# SCH_ESP32-S2-UNO_Final_2023-12-28.net
KiCad netlist of a schematic drawn in EasyEDA
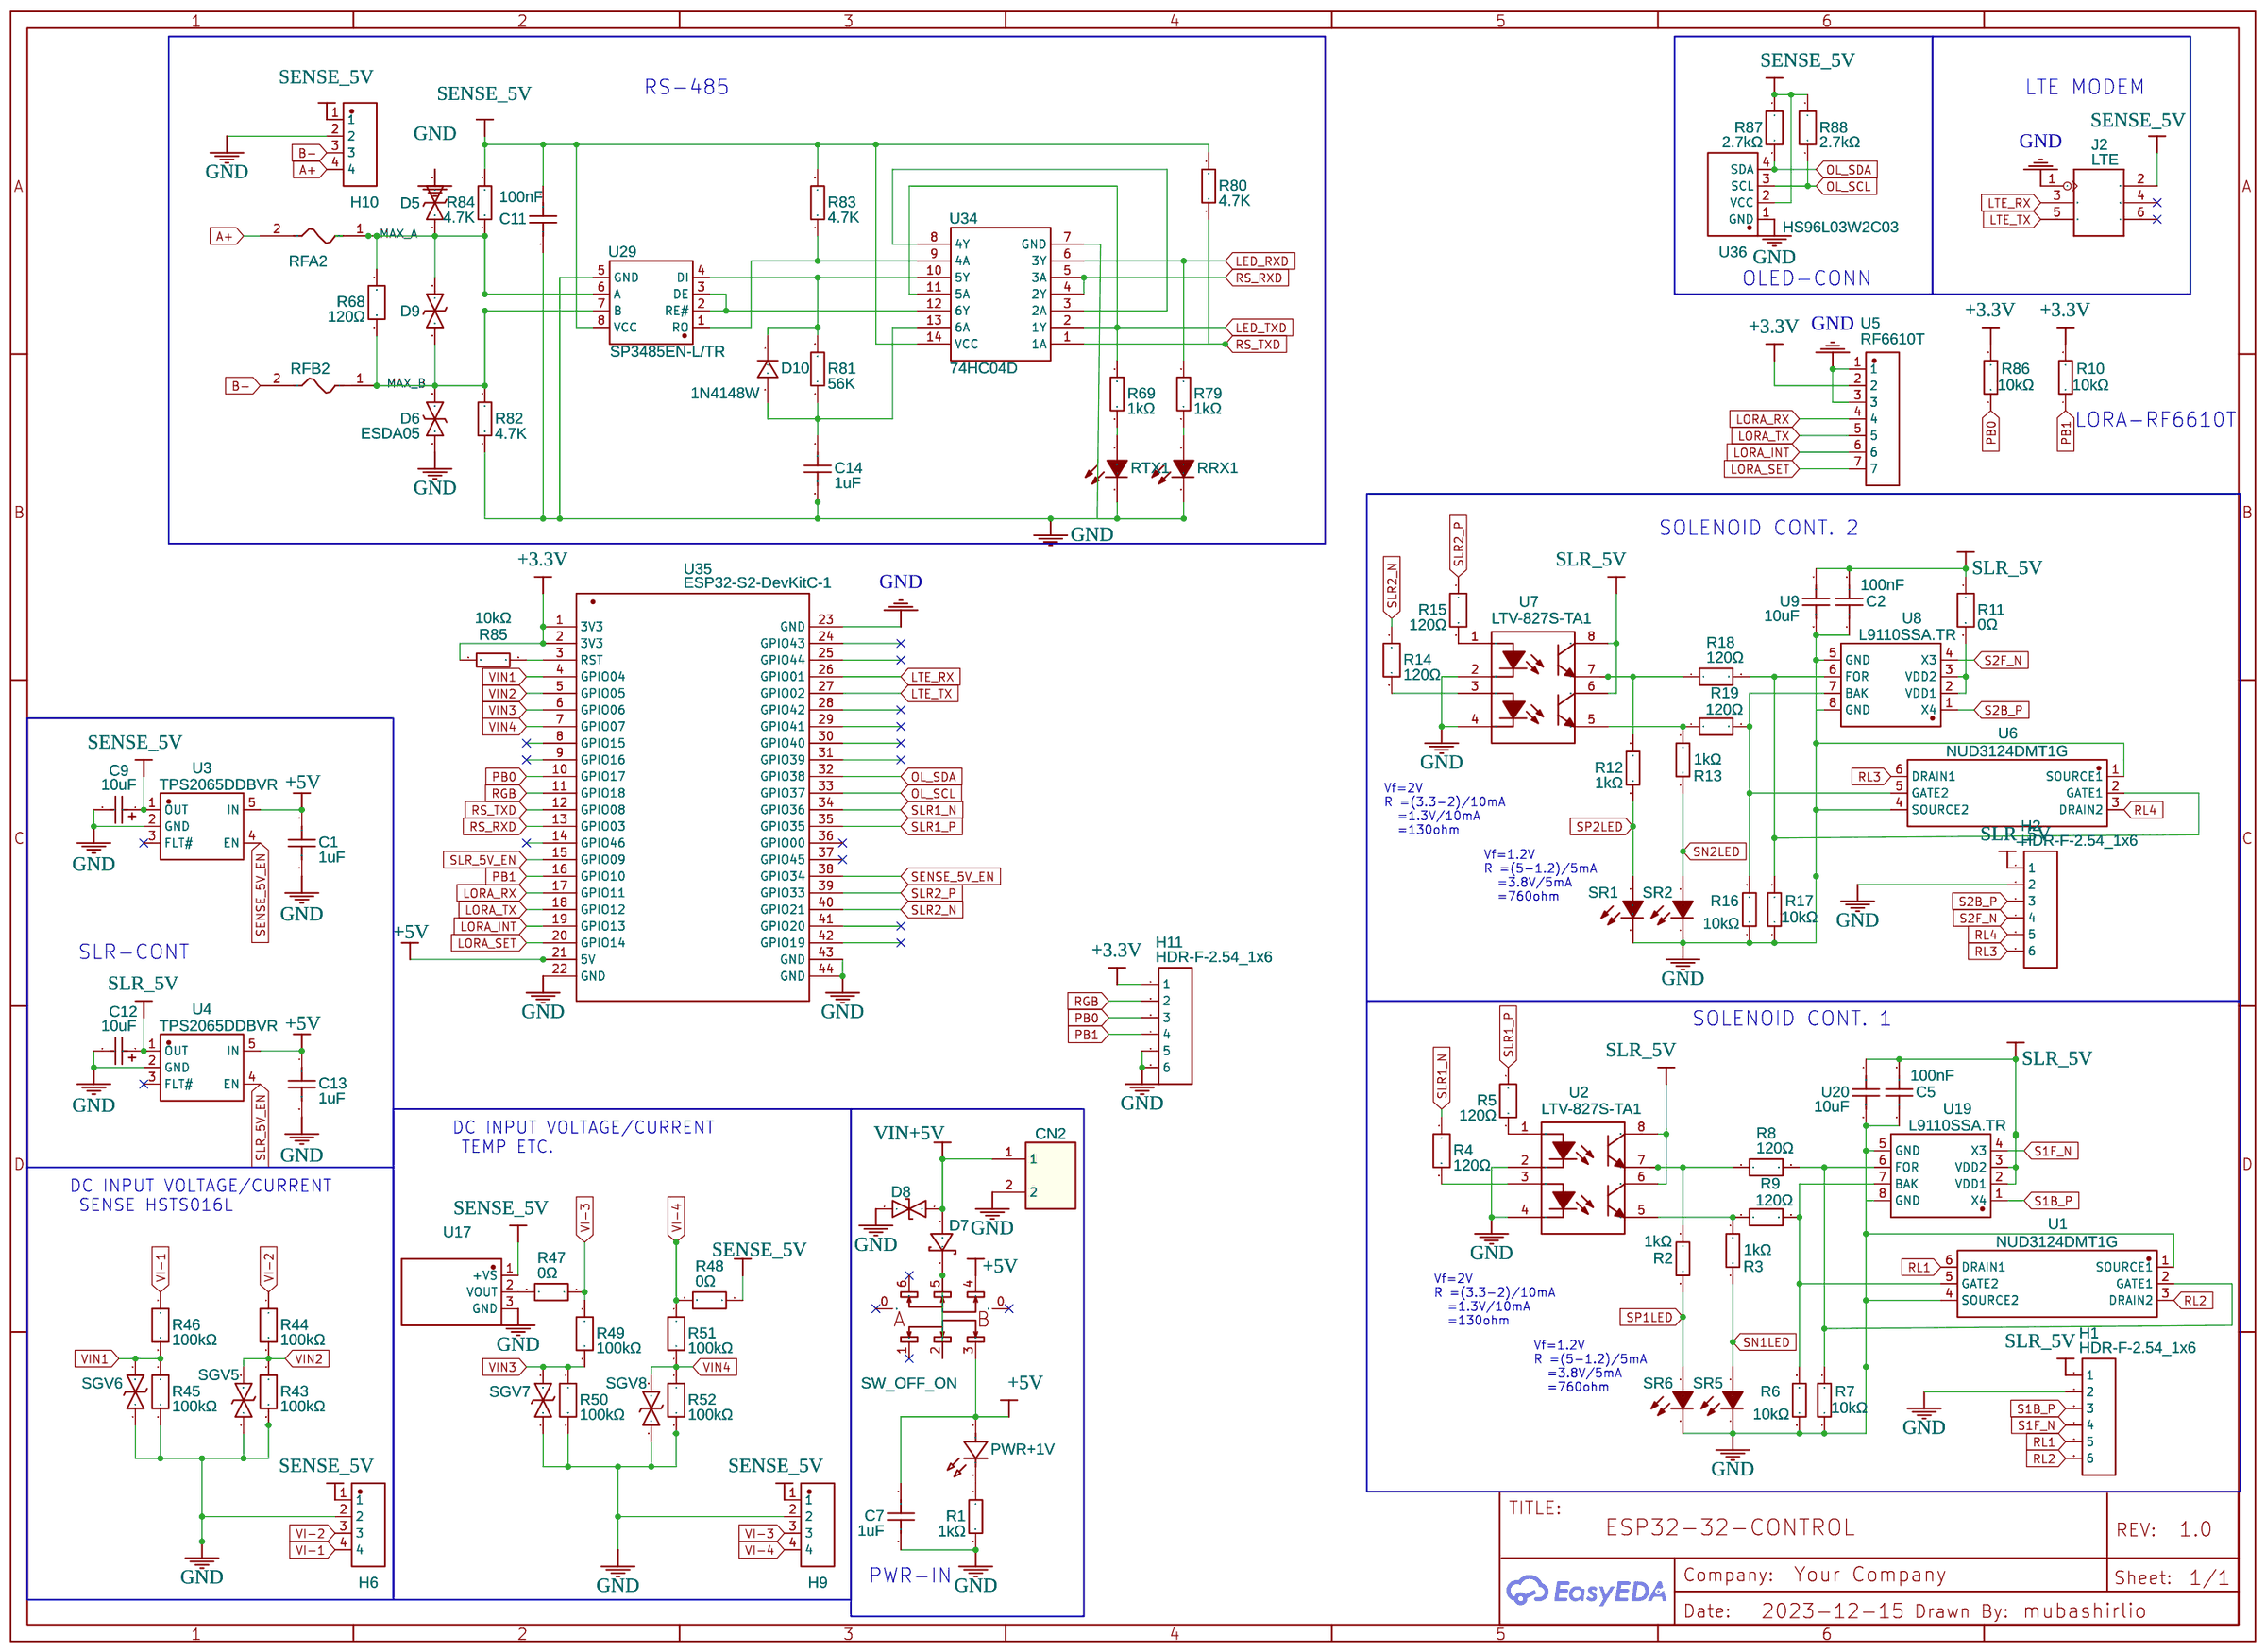
[diagram p0: schematic sheet]

(export (version "E")
  (design (tool "Eeschema 10.0.6"))
  (components
    (comp (ref "C1")
      (value "1uF")
      (fields
        (field (name "Manufacturer Part") "GRM155R61H105ME05D")
        (field (name "Manufacturer") "muRata(村田)")
      )
      (libsource (lib "") (part "GRM155R61H105ME05D"))
    )
    (comp (ref "C2")
      (value "100nF")
      (fields (field (name "Manufacturer Part") "C1005X5R0J104K050BA") (field (name "Manufacturer") "TDK"))
      (libsource (lib "") (part "C1005X5R0J104K050BA"))
    )
    (comp (ref "C5")
      (value "100nF")
      (fields (field (name "Manufacturer Part") "C1005X5R0J104K050BA") (field (name "Manufacturer") "TDK"))
      (libsource (lib "") (part "C1005X5R0J104K050BA"))
    )
    (comp (ref "C7")
      (value "1uF")
      (fields
        (field (name "Manufacturer Part") "GRM155R61H105ME05D")
        (field (name "Manufacturer") "muRata(村田)")
      )
      (libsource (lib "") (part "GRM155R61H105ME05D_1"))
    )
    (comp (ref "C9")
      (value "10uF")
      (fields
        (field (name "Manufacturer Part") "CA45A-A-16V-10uF-K")
        (field (name "Manufacturer") "CEC(振华新云)")
      )
      (libsource (lib "") (part "CA45A-A-16V-10UF-K"))
    )
    (comp (ref "C11")
      (value "100nF")
      (fields (field (name "Manufacturer Part") "C1005X5R0J104K050BA") (field (name "Manufacturer") "TDK"))
      (libsource (lib "") (part "C1005X5R0J104K050BA_1"))
    )
    (comp (ref "C12")
      (value "10uF")
      (fields
        (field (name "Manufacturer Part") "CA45A-A-16V-10uF-K")
        (field (name "Manufacturer") "CEC(振华新云)")
      )
      (libsource (lib "") (part "CA45A-A-16V-10UF-K"))
    )
    (comp (ref "C13")
      (value "1uF")
      (fields
        (field (name "Manufacturer Part") "GRM155R61H105ME05D")
        (field (name "Manufacturer") "muRata(村田)")
      )
      (libsource (lib "") (part "GRM155R61H105ME05D"))
    )
    (comp (ref "C14")
      (value "1uF")
      (fields
        (field (name "Manufacturer Part") "GRM155R61H105ME05D")
        (field (name "Manufacturer") "muRata(村田)")
      )
      (libsource (lib "") (part "GRM155R61H105ME05D"))
    )
    (comp (ref "CN2")
      (value "B2B-PH-K-S(LF)(SN)")
      (fields (field (name "Manufacturer") "JST"))
      (libsource (lib "") (part "B2B-PH-K-S(LF)(SN)"))
    )
    (comp (ref "D5")
      (value "ESDA05")
      (fields (field (name "Manufacturer") "Leiditech(雷卯电子)"))
      (libsource (lib "") (part "ESDA05_2"))
    )
    (comp (ref "D6")
      (value "ESDA05")
      (fields (field (name "Manufacturer") "Leiditech(雷卯电子)"))
      (libsource (lib "") (part "ESDA05_1"))
    )
    (comp (ref "D7")
      (value "BAT760-7")
      (fields (field (name "Manufacturer") "DIODES(美台)"))
      (libsource (lib "") (part "BAT760-7"))
    )
    (comp (ref "D8")
      (value "LESD5D5.0CT1G")
      (fields (field (name "Manufacturer") "LRC(乐山无线电)"))
      (libsource (lib "") (part "LESD5D5.0CT1G"))
    )
    (comp (ref "D9")
      (value "ESDA05")
      (fields (field (name "Manufacturer") "Leiditech(雷卯电子)"))
      (libsource (lib "") (part "ESDA05_2"))
    )
    (comp (ref "D10")
      (value "1N4148W")
      (fields (field (name "Manufacturer") "SEMTECH"))
      (libsource (lib "") (part "1N4148W_C81598"))
    )
    (comp (ref "H1") (value "HDR-F-2.54_1x6") (libsource (lib "") (part "HDR-F-2.54_1x6")))
    (comp (ref "H2") (value "HDR-F-2.54_1x6") (libsource (lib "") (part "HDR-F-2.54_1x6")))
    (comp (ref "H6")
      (value "X6511WV-04H-C30D60")
      (fields (field (name "Manufacturer") "XKB Connectivity(中国星坤)"))
      (libsource (lib "") (part "X6511WV-04H-C30D60"))
    )
    (comp (ref "H9")
      (value "X6511WV-04H-C30D60")
      (fields (field (name "Manufacturer") "XKB Connectivity(中国星坤)"))
      (libsource (lib "") (part "X6511WV-04H-C30D60"))
    )
    (comp (ref "H10")
      (value "X6511WV-04H-C30D60")
      (fields (field (name "Manufacturer") "XKB Connectivity(中国星坤)"))
      (libsource (lib "") (part "X6511WV-04H-C30D60"))
    )
    (comp (ref "H11") (value "HDR-F-2.54_1x6") (libsource (lib "") (part "HDR-F-2.54_1x6")))
    (comp (ref "J2") (value "LTE") (libsource (lib "") (part "MALE-HEADER(2X3P-2.54)")))
    (comp (ref "PWR+1V")
      (value "16-213/BHC-ZL1M2B6Y/3T")
      (fields (field (name "Manufacturer") "EVERLIGHT(亿光)"))
      (libsource (lib "") (part "16-213/BHC-ZL1M2B6Y/3T"))
    )
    (comp (ref "R1")
      (value "1kΩ")
      (fields (field (name "Manufacturer Part") "AR02DTD1001") (field (name "Manufacturer") "Viking(光颉)"))
      (libsource (lib "") (part "AR02DTD1001"))
    )
    (comp (ref "R2")
      (value "1kΩ")
      (fields (field (name "Manufacturer Part") "AR02DTD1001") (field (name "Manufacturer") "Viking(光颉)"))
      (libsource (lib "") (part "AR02DTD1001"))
    )
    (comp (ref "R3")
      (value "1kΩ")
      (fields (field (name "Manufacturer Part") "AR02DTD1001") (field (name "Manufacturer") "Viking(光颉)"))
      (libsource (lib "") (part "AR02DTD1001"))
    )
    (comp (ref "R4")
      (value "120Ω")
      (fields (field (name "Manufacturer Part") "RM04FTN1200") (field (name "Manufacturer") "大毅科技"))
      (libsource (lib "") (part "RM04FTN1200"))
    )
    (comp (ref "R5")
      (value "120Ω")
      (fields (field (name "Manufacturer Part") "RM04FTN1200") (field (name "Manufacturer") "大毅科技"))
      (libsource (lib "") (part "RM04FTN1200"))
    )
    (comp (ref "R6")
      (value "10kΩ")
      (fields
        (field (name "Manufacturer Part") "0402WGF1002TCE")
        (field (name "Manufacturer") "UNI-ROYAL(厚声)")
      )
      (libsource (lib "") (part "0402WGF1002TCE"))
    )
    (comp (ref "R7")
      (value "10kΩ")
      (fields
        (field (name "Manufacturer Part") "0402WGF1002TCE")
        (field (name "Manufacturer") "UNI-ROYAL(厚声)")
      )
      (libsource (lib "") (part "0402WGF1002TCE"))
    )
    (comp (ref "R8")
      (value "120Ω")
      (fields (field (name "Manufacturer Part") "RM04FTN1200") (field (name "Manufacturer") "大毅科技"))
      (libsource (lib "") (part "RM04FTN1200_1"))
    )
    (comp (ref "R9")
      (value "120Ω")
      (fields (field (name "Manufacturer Part") "RM04FTN1200") (field (name "Manufacturer") "大毅科技"))
      (libsource (lib "") (part "RM04FTN1200_1"))
    )
    (comp (ref "R10")
      (value "10kΩ")
      (fields
        (field (name "Manufacturer Part") "0402WGF1002TCE")
        (field (name "Manufacturer") "UNI-ROYAL(厚声)")
      )
      (libsource (lib "") (part "0402WGF1002TCE"))
    )
    (comp (ref "R11")
      (value "0Ω")
      (fields (field (name "Manufacturer Part") "CR-03JA7----0R") (field (name "Manufacturer") "Viking(光颉)"))
      (libsource (lib "") (part "CR-03JA7----0R_1"))
    )
    (comp (ref "R12")
      (value "1kΩ")
      (fields (field (name "Manufacturer Part") "AR02DTD1001") (field (name "Manufacturer") "Viking(光颉)"))
      (libsource (lib "") (part "AR02DTD1001"))
    )
    (comp (ref "R13")
      (value "1kΩ")
      (fields (field (name "Manufacturer Part") "AR02DTD1001") (field (name "Manufacturer") "Viking(光颉)"))
      (libsource (lib "") (part "AR02DTD1001"))
    )
    (comp (ref "R14")
      (value "120Ω")
      (fields (field (name "Manufacturer Part") "RM04FTN1200") (field (name "Manufacturer") "大毅科技"))
      (libsource (lib "") (part "RM04FTN1200"))
    )
    (comp (ref "R15")
      (value "120Ω")
      (fields (field (name "Manufacturer Part") "RM04FTN1200") (field (name "Manufacturer") "大毅科技"))
      (libsource (lib "") (part "RM04FTN1200"))
    )
    (comp (ref "R16")
      (value "10kΩ")
      (fields
        (field (name "Manufacturer Part") "0402WGF1002TCE")
        (field (name "Manufacturer") "UNI-ROYAL(厚声)")
      )
      (libsource (lib "") (part "0402WGF1002TCE"))
    )
    (comp (ref "R17")
      (value "10kΩ")
      (fields
        (field (name "Manufacturer Part") "0402WGF1002TCE")
        (field (name "Manufacturer") "UNI-ROYAL(厚声)")
      )
      (libsource (lib "") (part "0402WGF1002TCE"))
    )
    (comp (ref "R18")
      (value "120Ω")
      (fields (field (name "Manufacturer Part") "RM04FTN1200") (field (name "Manufacturer") "大毅科技"))
      (libsource (lib "") (part "RM04FTN1200_1"))
    )
    (comp (ref "R19")
      (value "120Ω")
      (fields (field (name "Manufacturer Part") "RM04FTN1200") (field (name "Manufacturer") "大毅科技"))
      (libsource (lib "") (part "RM04FTN1200_1"))
    )
    (comp (ref "R43")
      (value "100kΩ")
      (fields
        (field (name "Manufacturer Part") "CQ02WGJ0104TCE")
        (field (name "Manufacturer") "UNI-ROYAL(厚声)")
      )
      (libsource (lib "") (part "CQ02WGJ0104TCE"))
    )
    (comp (ref "R44")
      (value "100kΩ")
      (fields
        (field (name "Manufacturer Part") "CQ02WGJ0104TCE")
        (field (name "Manufacturer") "UNI-ROYAL(厚声)")
      )
      (libsource (lib "") (part "CQ02WGJ0104TCE"))
    )
    (comp (ref "R45")
      (value "100kΩ")
      (fields
        (field (name "Manufacturer Part") "CQ02WGJ0104TCE")
        (field (name "Manufacturer") "UNI-ROYAL(厚声)")
      )
      (libsource (lib "") (part "CQ02WGJ0104TCE"))
    )
    (comp (ref "R46")
      (value "100kΩ")
      (fields
        (field (name "Manufacturer Part") "CQ02WGJ0104TCE")
        (field (name "Manufacturer") "UNI-ROYAL(厚声)")
      )
      (libsource (lib "") (part "CQ02WGJ0104TCE"))
    )
    (comp (ref "R47")
      (value "0Ω")
      (fields (field (name "Manufacturer Part") "CR-03JA7----0R") (field (name "Manufacturer") "Viking(光颉)"))
      (libsource (lib "") (part "CR-03JA7----0R"))
    )
    (comp (ref "R48")
      (value "0Ω")
      (fields (field (name "Manufacturer Part") "CR-03JA7----0R") (field (name "Manufacturer") "Viking(光颉)"))
      (libsource (lib "") (part "CR-03JA7----0R"))
    )
    (comp (ref "R49")
      (value "100kΩ")
      (fields
        (field (name "Manufacturer Part") "CQ02WGJ0104TCE")
        (field (name "Manufacturer") "UNI-ROYAL(厚声)")
      )
      (libsource (lib "") (part "CQ02WGJ0104TCE"))
    )
    (comp (ref "R50")
      (value "100kΩ")
      (fields
        (field (name "Manufacturer Part") "CQ02WGJ0104TCE")
        (field (name "Manufacturer") "UNI-ROYAL(厚声)")
      )
      (libsource (lib "") (part "CQ02WGJ0104TCE"))
    )
    (comp (ref "R51")
      (value "100kΩ")
      (fields
        (field (name "Manufacturer Part") "CQ02WGJ0104TCE")
        (field (name "Manufacturer") "UNI-ROYAL(厚声)")
      )
      (libsource (lib "") (part "CQ02WGJ0104TCE"))
    )
    (comp (ref "R52")
      (value "100kΩ")
      (fields
        (field (name "Manufacturer Part") "CQ02WGJ0104TCE")
        (field (name "Manufacturer") "UNI-ROYAL(厚声)")
      )
      (libsource (lib "") (part "CQ02WGJ0104TCE"))
    )
    (comp (ref "R68")
      (value "120Ω")
      (fields (field (name "Manufacturer Part") "FRC0603J121 TS") (field (name "Manufacturer") "FOJAN(富捷)"))
      (libsource (lib "") (part "FRC0603J121 TS"))
    )
    (comp (ref "R69")
      (value "1kΩ")
      (fields (field (name "Manufacturer Part") "AR02DTD1001") (field (name "Manufacturer") "Viking(光颉)"))
      (libsource (lib "") (part "AR02DTD1001"))
    )
    (comp (ref "R79")
      (value "1kΩ")
      (fields (field (name "Manufacturer Part") "AR02DTD1001") (field (name "Manufacturer") "Viking(光颉)"))
      (libsource (lib "") (part "AR02DTD1001"))
    )
    (comp (ref "R80")
      (value "4.7K")
      (fields (field (name "Manufacturer Part") "0603WAF4701T5E") (field (name "Manufacturer") "UniOhm"))
      (libsource (lib "") (part "0603WAF4701T5E"))
    )
    (comp (ref "R81")
      (value "56K")
      (fields (field (name "Manufacturer Part") "0603WAF5602T5E") (field (name "Manufacturer") "UniOhm"))
      (libsource (lib "") (part "0603WAF5602T5E"))
    )
    (comp (ref "R82")
      (value "4.7K")
      (fields (field (name "Manufacturer Part") "0603WAF4701T5E") (field (name "Manufacturer") "UniOhm"))
      (libsource (lib "") (part "0603WAF4701T5E"))
    )
    (comp (ref "R83")
      (value "4.7K")
      (fields (field (name "Manufacturer Part") "0603WAF4701T5E") (field (name "Manufacturer") "UniOhm"))
      (libsource (lib "") (part "0603WAF4701T5E"))
    )
    (comp (ref "R84")
      (value "4.7K")
      (fields (field (name "Manufacturer Part") "0603WAF4701T5E") (field (name "Manufacturer") "UniOhm"))
      (libsource (lib "") (part "0603WAF4701T5E"))
    )
    (comp (ref "R85")
      (value "10kΩ")
      (fields
        (field (name "Manufacturer Part") "0402WGF1002TCE")
        (field (name "Manufacturer") "UNI-ROYAL(厚声)")
      )
      (libsource (lib "") (part "0402WGF1002TCE_1"))
    )
    (comp (ref "R86")
      (value "10kΩ")
      (fields
        (field (name "Manufacturer Part") "0402WGF1002TCE")
        (field (name "Manufacturer") "UNI-ROYAL(厚声)")
      )
      (libsource (lib "") (part "0402WGF1002TCE"))
    )
    (comp (ref "R87")
      (value "2.7kΩ")
      (fields (field (name "Manufacturer Part") "CR-02FL6---2K7") (field (name "Manufacturer") "Viking(光颉)"))
      (libsource (lib "") (part "CR-02FL6---2K7"))
    )
    (comp (ref "R88")
      (value "2.7kΩ")
      (fields (field (name "Manufacturer Part") "CR-02FL6---2K7") (field (name "Manufacturer") "Viking(光颉)"))
      (libsource (lib "") (part "CR-02FL6---2K7"))
    )
    (comp (ref "RFA2")
      (value "MF-MSMF010-2")
      (fields (field (name "Manufacturer") "BOURNS"))
      (libsource (lib "") (part "MF-MSMF010-2_1"))
    )
    (comp (ref "RFB2")
      (value "MF-MSMF010-2")
      (fields (field (name "Manufacturer") "BOURNS"))
      (libsource (lib "") (part "MF-MSMF010-2"))
    )
    (comp (ref "RRX1")
      (value "16-213/GHC-YR1S1/3T")
      (fields (field (name "Manufacturer") "EVERLIGHT(亿光)"))
      (libsource (lib "") (part "16-213/GHC-YR1S1/3T"))
    )
    (comp (ref "RTX1")
      (value "16-213/SDRC/S530-A3/TR8")
      (fields
        (field (name "Manufacturer Part") "16-213SDRC/S530-A3/TR8")
        (field (name "Manufacturer") "EVERLIGHT(亿光)")
      )
      (libsource (lib "") (part "16-213/SDRC/S530-A3/TR8"))
    )
    (comp (ref "SGV5")
      (value "ESDA05")
      (fields (field (name "Manufacturer") "Leiditech(雷卯电子)"))
      (libsource (lib "") (part "ESDA05"))
    )
    (comp (ref "SGV6")
      (value "ESDA05")
      (fields (field (name "Manufacturer") "Leiditech(雷卯电子)"))
      (libsource (lib "") (part "ESDA05"))
    )
    (comp (ref "SGV7")
      (value "ESDA05")
      (fields (field (name "Manufacturer") "Leiditech(雷卯电子)"))
      (libsource (lib "") (part "ESDA05"))
    )
    (comp (ref "SGV8")
      (value "ESDA05")
      (fields (field (name "Manufacturer") "Leiditech(雷卯电子)"))
      (libsource (lib "") (part "ESDA05"))
    )
    (comp (ref "SR1")
      (value "16-213/GHC-YR1S1/3T")
      (fields (field (name "Manufacturer") "EVERLIGHT(亿光)"))
      (libsource (lib "") (part "16-213/GHC-YR1S1/3T_1"))
    )
    (comp (ref "SR2")
      (value "16-213/SDRC/S530-A3/TR8")
      (fields
        (field (name "Manufacturer Part") "16-213SDRC/S530-A3/TR8")
        (field (name "Manufacturer") "EVERLIGHT(亿光)")
      )
      (libsource (lib "") (part "16-213/SDRC/S530-A3/TR8_1"))
    )
    (comp (ref "SR5")
      (value "16-213/SDRC/S530-A3/TR8")
      (fields
        (field (name "Manufacturer Part") "16-213SDRC/S530-A3/TR8")
        (field (name "Manufacturer") "EVERLIGHT(亿光)")
      )
      (libsource (lib "") (part "16-213/SDRC/S530-A3/TR8_1"))
    )
    (comp (ref "SR6")
      (value "16-213/GHC-YR1S1/3T")
      (fields (field (name "Manufacturer") "EVERLIGHT(亿光)"))
      (libsource (lib "") (part "16-213/GHC-YR1S1/3T_1"))
    )
    (comp (ref "SW2")
      (value "SW_OFF_ON")
      (fields (field (name "Manufacturer Part") "TA-3519S-A1") (field (name "Manufacturer") "Yuandi(元迪)"))
      (libsource (lib "") (part "TA-3519S-A1"))
    )
    (comp (ref "U1")
      (value "NUD3124DMT1G")
      (fields (field (name "Manufacturer") "ON Semicon"))
      (libsource (lib "") (part "NUD3124DMT1G"))
    )
    (comp (ref "U2")
      (value "LTV-827S-TA1")
      (fields (field (name "Manufacturer") "LITEON"))
      (libsource (lib "") (part "Unknown_-1235_-1295"))
    )
    (comp (ref "U3")
      (value "TPS2065DDBVR")
      (fields (field (name "Manufacturer") "TI(德州仪器)"))
      (libsource (lib "") (part "TPS2065DDBVR"))
    )
    (comp (ref "U4")
      (value "TPS2065DDBVR")
      (fields (field (name "Manufacturer") "TI(德州仪器)"))
      (libsource (lib "") (part "TPS2065DDBVR"))
    )
    (comp (ref "U5")
      (value "RF6610T")
      (fields
        (field (name "Manufacturer Part") "PM254-1-07-Z-8.5")
        (field (name "Manufacturer") "HCTL(华灿天禄)")
      )
      (libsource (lib "") (part "RF6610T"))
    )
    (comp (ref "U6")
      (value "NUD3124DMT1G")
      (fields (field (name "Manufacturer") "ON Semicon"))
      (libsource (lib "") (part "NUD3124DMT1G"))
    )
    (comp (ref "U7")
      (value "LTV-827S-TA1")
      (fields (field (name "Manufacturer") "LITEON"))
      (libsource (lib "") (part "Unknown_-1265_-1590"))
    )
    (comp (ref "U8")
      (value "L9110SSA.TR")
      (fields (field (name "Manufacturer") "I-CORE(中微爱芯)"))
      (libsource (lib "") (part "L9110SSA.TR"))
    )
    (comp (ref "U9")
      (value "10uF")
      (fields (field (name "Manufacturer Part") "CGB3C1JB0J106M065AC") (field (name "Manufacturer") "TDK"))
      (libsource (lib "") (part "CGB3C1JB0J106M065AC"))
    )
    (comp (ref "U17")
      (value "LM35DZ/LFT1")
      (fields (field (name "Manufacturer") "TI(德州仪器)"))
      (libsource (lib "") (part "LM35DZ/LFT1"))
    )
    (comp (ref "U19")
      (value "L9110SSA.TR")
      (fields (field (name "Manufacturer") "I-CORE(中微爱芯)"))
      (libsource (lib "") (part "L9110SSA.TR"))
    )
    (comp (ref "U20")
      (value "10uF")
      (fields (field (name "Manufacturer Part") "CGB3C1JB0J106M065AC") (field (name "Manufacturer") "TDK"))
      (libsource (lib "") (part "CGB3C1JB0J106M065AC"))
    )
    (comp (ref "U29")
      (value "SP3485EN-L/TR")
      (fields (field (name "Manufacturer") "EXAR"))
      (libsource (lib "") (part "SP3485EN-L/TR"))
    )
    (comp (ref "U34")
      (value "74HC04D")
      (fields (field (name "Manufacturer Part") "74HC04D,653") (field (name "Manufacturer") "Nexperia"))
      (libsource (lib "") (part "Unknown_-1590_-1830"))
    )
    (comp (ref "U35")
      (value "ESP32-S2-DevKitC-1")
      (fields (field (name "Manufacturer") "Espressif Manifacturer"))
      (libsource (lib "") (part "ESP32-S2-DevKitC-1"))
    )
    (comp (ref "U36")
      (value "HS96L03W2C03")
      (fields (field (name "Manufacturer") "HS(汉昇)"))
      (libsource (lib "") (part "HS96L03W2C03"))
    )
  )
  (nets
    (net (code "1") (name "+3.3V") (class "Default")
      (node (ref "H11") (pin "1") (pinfunction "1_1") (pintype "input"))
      (node (ref "R10") (pin "2") (pinfunction "2_2") (pintype "input"))
      (node (ref "R85") (pin "1") (pinfunction "1_1") (pintype "input"))
      (node (ref "R86") (pin "2") (pinfunction "2_2") (pintype "input"))
      (node (ref "U35") (pin "1") (pinfunction "3V3_1") (pintype "passive"))
      (node (ref "U35") (pin "2") (pinfunction "3V3_2") (pintype "passive"))
      (node (ref "U5") (pin "2") (pinfunction "2_2") (pintype "unspecified"))
    )
    (net (code "2") (name "+5V") (class "Default")
      (node (ref "C1") (pin "1") (pinfunction "1_1") (pintype "unspecified"))
      (node (ref "C13") (pin "1") (pinfunction "1_1") (pintype "unspecified"))
      (node (ref "C7") (pin "1") (pinfunction "1_1") (pintype "unspecified"))
      (node (ref "PWR+1V") (pin "2") (pinfunction "A_2") (pintype "unspecified"))
      (node (ref "SW2") (pin "3") (pinfunction "3_3") (pintype "unspecified"))
      (node (ref "SW2") (pin "4") (pinfunction "4_4") (pintype "unspecified"))
      (node (ref "U3") (pin "5") (pinfunction "IN_5") (pintype "unspecified"))
      (node (ref "U35") (pin "21") (pinfunction "5V_21") (pintype "passive"))
      (node (ref "U4") (pin "5") (pinfunction "IN_5") (pintype "unspecified"))
    )
    (net (code "3") (name "/MAX_A") (class "Default")
      (node (ref "D5") (pin "2") (pinfunction "2_2") (pintype "unspecified"))
      (node (ref "D9") (pin "1") (pinfunction "1_1") (pintype "unspecified"))
      (node (ref "R68") (pin "1") (pinfunction "1_1") (pintype "unspecified"))
      (node (ref "R84") (pin "1") (pinfunction "1_1") (pintype "input"))
      (node (ref "RFA2") (pin "1") (pinfunction "1_1") (pintype "unspecified"))
      (node (ref "U29") (pin "6") (pinfunction "A_6") (pintype "unspecified"))
    )
    (net (code "4") (name "/MAX_B") (class "Default")
      (node (ref "D6") (pin "2") (pinfunction "2_2") (pintype "unspecified"))
      (node (ref "D9") (pin "2") (pinfunction "2_2") (pintype "unspecified"))
      (node (ref "R68") (pin "2") (pinfunction "2_2") (pintype "unspecified"))
      (node (ref "R82") (pin "2") (pinfunction "2_2") (pintype "input"))
      (node (ref "RFB2") (pin "1") (pinfunction "1_1") (pintype "unspecified"))
      (node (ref "U29") (pin "7") (pinfunction "B_7") (pintype "unspecified"))
    )
    (net (code "5") (name "A+") (class "Default")
      (node (ref "H10") (pin "4") (pinfunction "4_4") (pintype "unspecified"))
      (node (ref "RFA2") (pin "2") (pinfunction "2_2") (pintype "unspecified"))
    )
    (net (code "6") (name "B-") (class "Default")
      (node (ref "H10") (pin "3") (pinfunction "3_3") (pintype "unspecified"))
      (node (ref "RFB2") (pin "2") (pinfunction "2_2") (pintype "unspecified"))
    )
    (net (code "7") (name "GND") (class "Default")
      (node (ref "C1") (pin "2") (pinfunction "2_2") (pintype "unspecified"))
      (node (ref "C11") (pin "1") (pinfunction "1_1") (pintype "unspecified"))
      (node (ref "C12") (pin "2") (pinfunction "2_2") (pintype "input"))
      (node (ref "C13") (pin "2") (pinfunction "2_2") (pintype "unspecified"))
      (node (ref "C14") (pin "2") (pinfunction "2_2") (pintype "unspecified"))
      (node (ref "C2") (pin "1") (pinfunction "1_1") (pintype "unspecified"))
      (node (ref "C5") (pin "1") (pinfunction "1_1") (pintype "unspecified"))
      (node (ref "C7") (pin "2") (pinfunction "2_2") (pintype "unspecified"))
      (node (ref "C9") (pin "2") (pinfunction "2_2") (pintype "input"))
      (node (ref "CN2") (pin "2") (pinfunction "2_2") (pintype "input"))
      (node (ref "D5") (pin "1") (pinfunction "1_1") (pintype "unspecified"))
      (node (ref "D6") (pin "1") (pinfunction "1_1") (pintype "unspecified"))
      (node (ref "D8") (pin "1") (pinfunction "1_1") (pintype "unspecified"))
      (node (ref "H1") (pin "2") (pinfunction "2_2") (pintype "input"))
      (node (ref "H10") (pin "2") (pinfunction "2_2") (pintype "unspecified"))
      (node (ref "H11") (pin "5") (pinfunction "5_5") (pintype "input"))
      (node (ref "H11") (pin "6") (pinfunction "6_6") (pintype "input"))
      (node (ref "H2") (pin "2") (pinfunction "2_2") (pintype "input"))
      (node (ref "H6") (pin "2") (pinfunction "2_2") (pintype "unspecified"))
      (node (ref "H9") (pin "2") (pinfunction "2_2") (pintype "unspecified"))
      (node (ref "J2") (pin "1") (pinfunction "1_1") (pintype "bidirectional"))
      (node (ref "R1") (pin "2") (pinfunction "2_2") (pintype "unspecified"))
      (node (ref "R16") (pin "1") (pinfunction "1_1") (pintype "input"))
      (node (ref "R17") (pin "1") (pinfunction "1_1") (pintype "input"))
      (node (ref "R43") (pin "2") (pinfunction "2_2") (pintype "unspecified"))
      (node (ref "R45") (pin "2") (pinfunction "2_2") (pintype "unspecified"))
      (node (ref "R50") (pin "2") (pinfunction "2_2") (pintype "unspecified"))
      (node (ref "R52") (pin "2") (pinfunction "2_2") (pintype "unspecified"))
      (node (ref "R6") (pin "1") (pinfunction "1_1") (pintype "input"))
      (node (ref "R7") (pin "1") (pinfunction "1_1") (pintype "input"))
      (node (ref "R82") (pin "1") (pinfunction "1_1") (pintype "input"))
      (node (ref "RRX1") (pin "2") (pinfunction "C_2") (pintype "input"))
      (node (ref "RTX1") (pin "1") (pinfunction "-_1") (pintype "input"))
      (node (ref "SGV5") (pin "1") (pinfunction "1_1") (pintype "unspecified"))
      (node (ref "SGV6") (pin "1") (pinfunction "1_1") (pintype "unspecified"))
      (node (ref "SGV7") (pin "1") (pinfunction "1_1") (pintype "unspecified"))
      (node (ref "SGV8") (pin "1") (pinfunction "1_1") (pintype "unspecified"))
      (node (ref "SR1") (pin "2") (pinfunction "C_2") (pintype "input"))
      (node (ref "SR2") (pin "1") (pinfunction "-_1") (pintype "input"))
      (node (ref "SR5") (pin "1") (pinfunction "-_1") (pintype "input"))
      (node (ref "SR6") (pin "2") (pinfunction "C_2") (pintype "input"))
      (node (ref "U1") (pin "1") (pinfunction "SOURCE1_1") (pintype "unspecified"))
      (node (ref "U1") (pin "4") (pinfunction "SOURCE2_4") (pintype "unspecified"))
      (node (ref "U17") (pin "3") (pinfunction "GND_3") (pintype "unspecified"))
      (node (ref "U19") (pin "5") (pinfunction "GND_5") (pintype "unspecified"))
      (node (ref "U19") (pin "8") (pinfunction "GND_8") (pintype "unspecified"))
      (node (ref "U2") (pin "2") (pinfunction "2_2") (pintype "unspecified"))
      (node (ref "U2") (pin "4") (pinfunction "4_4") (pintype "unspecified"))
      (node (ref "U20") (pin "2") (pinfunction "2_2") (pintype "unspecified"))
      (node (ref "U29") (pin "5") (pinfunction "GND_5") (pintype "unspecified"))
      (node (ref "U3") (pin "2") (pinfunction "GND_2") (pintype "unspecified"))
      (node (ref "U34") (pin "7") (pinfunction "GND_7") (pintype "unspecified"))
      (node (ref "U35") (pin "22") (pinfunction "GND_22") (pintype "passive"))
      (node (ref "U35") (pin "23") (pinfunction "GND_23") (pintype "passive"))
      (node (ref "U35") (pin "43") (pinfunction "GND_43") (pintype "passive"))
      (node (ref "U35") (pin "44") (pinfunction "GND_44") (pintype "passive"))
      (node (ref "U36") (pin "1") (pinfunction "GND_1") (pintype "unspecified"))
      (node (ref "U4") (pin "2") (pinfunction "GND_2") (pintype "unspecified"))
      (node (ref "U5") (pin "1") (pinfunction "1_1") (pintype "unspecified"))
      (node (ref "U5") (pin "3") (pinfunction "3_3") (pintype "unspecified"))
      (node (ref "U6") (pin "1") (pinfunction "SOURCE1_1") (pintype "unspecified"))
      (node (ref "U6") (pin "4") (pinfunction "SOURCE2_4") (pintype "unspecified"))
      (node (ref "U7") (pin "2") (pinfunction "2_2") (pintype "unspecified"))
      (node (ref "U7") (pin "4") (pinfunction "4_4") (pintype "unspecified"))
      (node (ref "U8") (pin "5") (pinfunction "GND_5") (pintype "unspecified"))
      (node (ref "U8") (pin "8") (pinfunction "GND_8") (pintype "unspecified"))
      (node (ref "U9") (pin "2") (pinfunction "2_2") (pintype "unspecified"))
    )
    (net (code "8") (name "LED_RXD") (class "Default")
      (node (ref "R79") (pin "1") (pinfunction "1_1") (pintype "unspecified"))
      (node (ref "U34") (pin "6") (pinfunction "3Y_6") (pintype "unspecified"))
    )
    (net (code "9") (name "LED_TXD") (class "Default")
      (node (ref "R69") (pin "1") (pinfunction "1_1") (pintype "unspecified"))
      (node (ref "U34") (pin "11") (pinfunction "5A_11") (pintype "unspecified"))
      (node (ref "U34") (pin "2") (pinfunction "1Y_2") (pintype "unspecified"))
    )
    (net (code "10") (name "LORA_INT") (class "Default")
      (node (ref "U35") (pin "19") (pinfunction "GPIO13_19") (pintype "bidirectional"))
      (node (ref "U5") (pin "6") (pinfunction "6_6") (pintype "unspecified"))
    )
    (net (code "11") (name "LORA_RX") (class "Default")
      (node (ref "U35") (pin "17") (pinfunction "GPIO11_17") (pintype "bidirectional"))
      (node (ref "U5") (pin "4") (pinfunction "4_4") (pintype "unspecified"))
    )
    (net (code "12") (name "LORA_SET") (class "Default")
      (node (ref "U35") (pin "20") (pinfunction "GPIO14_20") (pintype "bidirectional"))
      (node (ref "U5") (pin "7") (pinfunction "7_7") (pintype "unspecified"))
    )
    (net (code "13") (name "LORA_TX") (class "Default")
      (node (ref "U35") (pin "18") (pinfunction "GPIO12_18") (pintype "bidirectional"))
      (node (ref "U5") (pin "5") (pinfunction "5_5") (pintype "unspecified"))
    )
    (net (code "14") (name "LTE_RX") (class "Default")
      (node (ref "J2") (pin "3") (pinfunction "2_3") (pintype "bidirectional"))
      (node (ref "U35") (pin "26") (pinfunction "GPIO01_26") (pintype "bidirectional"))
    )
    (net (code "15") (name "LTE_TX") (class "Default")
      (node (ref "J2") (pin "5") (pinfunction "3_5") (pintype "bidirectional"))
      (node (ref "U35") (pin "27") (pinfunction "GPIO02_27") (pintype "bidirectional"))
    )
    (net (code "16") (name "Net-(D7-Pad1)") (class "Default")
      (node (ref "D7") (pin "1") (pinfunction "1_1") (pintype "unspecified"))
      (node (ref "SW2") (pin "2") (pinfunction "2_2") (pintype "unspecified"))
      (node (ref "SW2") (pin "5") (pinfunction "5_5") (pintype "unspecified"))
    )
    (net (code "17") (name "Net-(D10-A)") (class "Default")
      (node (ref "C14") (pin "1") (pinfunction "1_1") (pintype "unspecified"))
      (node (ref "D10") (pin "2") (pinfunction "A_2") (pintype "unspecified"))
      (node (ref "R81") (pin "1") (pinfunction "1_1") (pintype "input"))
      (node (ref "U34") (pin "13") (pinfunction "6A_13") (pintype "unspecified"))
    )
    (net (code "18") (name "Net-(D10-K)") (class "Default")
      (node (ref "D10") (pin "1") (pinfunction "K_1") (pintype "unspecified"))
      (node (ref "R81") (pin "2") (pinfunction "2_2") (pintype "input"))
      (node (ref "U29") (pin "4") (pinfunction "DI_4") (pintype "unspecified"))
      (node (ref "U34") (pin "10") (pinfunction "5Y_10") (pintype "unspecified"))
    )
    (net (code "19") (name "Net-(PWR+1V-K)") (class "Default")
      (node (ref "PWR+1V") (pin "1") (pinfunction "K_1") (pintype "unspecified"))
      (node (ref "R1") (pin "1") (pinfunction "1_1") (pintype "unspecified"))
    )
    (net (code "20") (name "Net-(R2-Pad1)") (class "Default")
      (node (ref "R2") (pin "1") (pinfunction "1_1") (pintype "unspecified"))
      (node (ref "R8") (pin "1") (pinfunction "1_1") (pintype "unspecified"))
      (node (ref "U2") (pin "7") (pinfunction "7_7") (pintype "unspecified"))
    )
    (net (code "21") (name "Net-(R3-Pad1)") (class "Default")
      (node (ref "R3") (pin "1") (pinfunction "1_1") (pintype "unspecified"))
      (node (ref "R9") (pin "1") (pinfunction "1_1") (pintype "unspecified"))
      (node (ref "U2") (pin "5") (pinfunction "5_5") (pintype "unspecified"))
    )
    (net (code "22") (name "Net-(R4-Pad2)") (class "Default")
      (node (ref "R4") (pin "2") (pinfunction "2_2") (pintype "unspecified"))
      (node (ref "U2") (pin "3") (pinfunction "3_3") (pintype "unspecified"))
    )
    (net (code "23") (name "Net-(R5-Pad2)") (class "Default")
      (node (ref "R5") (pin "2") (pinfunction "2_2") (pintype "unspecified"))
      (node (ref "U2") (pin "1") (pinfunction "1_1") (pintype "unspecified"))
    )
    (net (code "24") (name "Net-(R12-Pad1)") (class "Default")
      (node (ref "R12") (pin "1") (pinfunction "1_1") (pintype "unspecified"))
      (node (ref "R18") (pin "1") (pinfunction "1_1") (pintype "unspecified"))
      (node (ref "U7") (pin "7") (pinfunction "7_7") (pintype "unspecified"))
    )
    (net (code "25") (name "Net-(R13-Pad1)") (class "Default")
      (node (ref "R13") (pin "1") (pinfunction "1_1") (pintype "unspecified"))
      (node (ref "R19") (pin "1") (pinfunction "1_1") (pintype "unspecified"))
      (node (ref "U7") (pin "5") (pinfunction "5_5") (pintype "unspecified"))
    )
    (net (code "26") (name "Net-(R14-Pad2)") (class "Default")
      (node (ref "R14") (pin "2") (pinfunction "2_2") (pintype "unspecified"))
      (node (ref "U7") (pin "3") (pinfunction "3_3") (pintype "unspecified"))
    )
    (net (code "27") (name "Net-(R15-Pad2)") (class "Default")
      (node (ref "R15") (pin "2") (pinfunction "2_2") (pintype "unspecified"))
      (node (ref "U7") (pin "1") (pinfunction "1_1") (pintype "unspecified"))
    )
    (net (code "28") (name "Net-(RRX1-A)") (class "Default")
      (node (ref "R79") (pin "2") (pinfunction "2_2") (pintype "unspecified"))
      (node (ref "RRX1") (pin "1") (pinfunction "A_1") (pintype "input"))
    )
    (net (code "29") (name "Net-(RTX1-+)") (class "Default")
      (node (ref "R69") (pin "2") (pinfunction "2_2") (pintype "unspecified"))
      (node (ref "RTX1") (pin "2") (pinfunction "+_2") (pintype "input"))
    )
    (net (code "30") (name "Net-(U1-GATE1)") (class "Default")
      (node (ref "R7") (pin "2") (pinfunction "2_2") (pintype "input"))
      (node (ref "R8") (pin "2") (pinfunction "2_2") (pintype "unspecified"))
      (node (ref "U1") (pin "2") (pinfunction "GATE1_2") (pintype "unspecified"))
      (node (ref "U19") (pin "6") (pinfunction "FOR_6") (pintype "unspecified"))
    )
    (net (code "31") (name "Net-(U1-GATE2)") (class "Default")
      (node (ref "R6") (pin "2") (pinfunction "2_2") (pintype "input"))
      (node (ref "R9") (pin "2") (pinfunction "2_2") (pintype "unspecified"))
      (node (ref "U1") (pin "5") (pinfunction "GATE2_5") (pintype "unspecified"))
      (node (ref "U19") (pin "7") (pinfunction "BAK_7") (pintype "unspecified"))
    )
    (net (code "32") (name "Net-(U6-GATE1)") (class "Default")
      (node (ref "R17") (pin "2") (pinfunction "2_2") (pintype "input"))
      (node (ref "R18") (pin "2") (pinfunction "2_2") (pintype "unspecified"))
      (node (ref "U6") (pin "2") (pinfunction "GATE1_2") (pintype "unspecified"))
      (node (ref "U8") (pin "6") (pinfunction "FOR_6") (pintype "unspecified"))
    )
    (net (code "33") (name "Net-(U6-GATE2)") (class "Default")
      (node (ref "R16") (pin "2") (pinfunction "2_2") (pintype "input"))
      (node (ref "R19") (pin "2") (pinfunction "2_2") (pintype "unspecified"))
      (node (ref "U6") (pin "5") (pinfunction "GATE2_5") (pintype "unspecified"))
      (node (ref "U8") (pin "7") (pinfunction "BAK_7") (pintype "unspecified"))
    )
    (net (code "34") (name "Net-(U8-VDD1)") (class "Default")
      (node (ref "R11") (pin "2") (pinfunction "2_2") (pintype "unspecified"))
      (node (ref "U8") (pin "2") (pinfunction "VDD1_2") (pintype "unspecified"))
      (node (ref "U8") (pin "3") (pinfunction "VDD2_3") (pintype "unspecified"))
    )
    (net (code "35") (name "Net-(U17-VOUT)") (class "Default")
      (node (ref "R47") (pin "2") (pinfunction "2_2") (pintype "unspecified"))
      (node (ref "U17") (pin "2") (pinfunction "VOUT_2") (pintype "unspecified"))
    )
    (net (code "36") (name "Net-(U29-DE)") (class "Default")
      (node (ref "U29") (pin "2") (pinfunction "RE#_2") (pintype "unspecified"))
      (node (ref "U29") (pin "3") (pinfunction "DE_3") (pintype "unspecified"))
      (node (ref "U34") (pin "12") (pinfunction "6Y_12") (pintype "unspecified"))
    )
    (net (code "37") (name "Net-(U29-RO)") (class "Default")
      (node (ref "R83") (pin "1") (pinfunction "1_1") (pintype "input"))
      (node (ref "U29") (pin "1") (pinfunction "RO_1") (pintype "unspecified"))
      (node (ref "U34") (pin "9") (pinfunction "4A_9") (pintype "unspecified"))
    )
    (net (code "38") (name "Net-(U34-2A)") (class "Default")
      (node (ref "U34") (pin "3") (pinfunction "2A_3") (pintype "unspecified"))
      (node (ref "U34") (pin "8") (pinfunction "4Y_8") (pintype "unspecified"))
    )
    (net (code "39") (name "Net-(U35-RST)") (class "Default")
      (node (ref "R85") (pin "2") (pinfunction "2_2") (pintype "input"))
      (node (ref "U35") (pin "3") (pinfunction "RST_3") (pintype "bidirectional"))
    )
    (net (code "40") (name "OL_SCL") (class "Default")
      (node (ref "R88") (pin "2") (pinfunction "2_2") (pintype "unspecified"))
      (node (ref "U35") (pin "33") (pinfunction "GPIO37_33") (pintype "bidirectional"))
      (node (ref "U36") (pin "3") (pinfunction "SCL_3") (pintype "unspecified"))
    )
    (net (code "41") (name "OL_SDA") (class "Default")
      (node (ref "R87") (pin "2") (pinfunction "2_2") (pintype "unspecified"))
      (node (ref "U35") (pin "32") (pinfunction "GPIO38_32") (pintype "bidirectional"))
      (node (ref "U36") (pin "4") (pinfunction "SDA_4") (pintype "unspecified"))
    )
    (net (code "42") (name "PB0") (class "Default")
      (node (ref "H11") (pin "3") (pinfunction "3_3") (pintype "input"))
      (node (ref "R86") (pin "1") (pinfunction "1_1") (pintype "input"))
      (node (ref "U35") (pin "10") (pinfunction "GPIO17_10") (pintype "bidirectional"))
    )
    (net (code "43") (name "PB1") (class "Default")
      (node (ref "H11") (pin "4") (pinfunction "4_4") (pintype "input"))
      (node (ref "R10") (pin "1") (pinfunction "1_1") (pintype "input"))
      (node (ref "U35") (pin "16") (pinfunction "GPIO10_16") (pintype "bidirectional"))
    )
    (net (code "44") (name "RGB") (class "Default")
      (node (ref "H11") (pin "2") (pinfunction "2_2") (pintype "input"))
      (node (ref "U35") (pin "11") (pinfunction "GPIO18_11") (pintype "bidirectional"))
    )
    (net (code "45") (name "RL1") (class "Default")
      (node (ref "H1") (pin "5") (pinfunction "5_5") (pintype "input"))
      (node (ref "U1") (pin "6") (pinfunction "DRAIN1_6") (pintype "unspecified"))
    )
    (net (code "46") (name "RL2") (class "Default")
      (node (ref "H1") (pin "6") (pinfunction "6_6") (pintype "input"))
      (node (ref "U1") (pin "3") (pinfunction "DRAIN2_3") (pintype "unspecified"))
    )
    (net (code "47") (name "RL3") (class "Default")
      (node (ref "H2") (pin "6") (pinfunction "6_6") (pintype "input"))
      (node (ref "U6") (pin "6") (pinfunction "DRAIN1_6") (pintype "unspecified"))
    )
    (net (code "48") (name "RL4") (class "Default")
      (node (ref "H2") (pin "5") (pinfunction "5_5") (pintype "input"))
      (node (ref "U6") (pin "3") (pinfunction "DRAIN2_3") (pintype "unspecified"))
    )
    (net (code "49") (name "RS_RXD") (class "Default")
      (node (ref "U34") (pin "4") (pinfunction "2Y_4") (pintype "unspecified"))
      (node (ref "U34") (pin "5") (pinfunction "3A_5") (pintype "unspecified"))
      (node (ref "U35") (pin "13") (pinfunction "GPIO03_13") (pintype "bidirectional"))
    )
    (net (code "50") (name "RS_TXD") (class "Default")
      (node (ref "R80") (pin "1") (pinfunction "1_1") (pintype "input"))
      (node (ref "U34") (pin "1") (pinfunction "1A_1") (pintype "unspecified"))
      (node (ref "U35") (pin "12") (pinfunction "GPIO08_12") (pintype "bidirectional"))
    )
    (net (code "51") (name "S1B_P") (class "Default")
      (node (ref "H1") (pin "3") (pinfunction "3_3") (pintype "input"))
      (node (ref "U19") (pin "1") (pinfunction "X4_1") (pintype "unspecified"))
    )
    (net (code "52") (name "S1F_N") (class "Default")
      (node (ref "H1") (pin "4") (pinfunction "4_4") (pintype "input"))
      (node (ref "U19") (pin "4") (pinfunction "X3_4") (pintype "unspecified"))
    )
    (net (code "53") (name "S2B_P") (class "Default")
      (node (ref "H2") (pin "3") (pinfunction "3_3") (pintype "input"))
      (node (ref "U8") (pin "1") (pinfunction "X4_1") (pintype "unspecified"))
    )
    (net (code "54") (name "S2F_N") (class "Default")
      (node (ref "H2") (pin "4") (pinfunction "4_4") (pintype "input"))
      (node (ref "U8") (pin "4") (pinfunction "X3_4") (pintype "unspecified"))
    )
    (net (code "55") (name "SENSE_5V") (class "Default")
      (node (ref "C11") (pin "2") (pinfunction "2_2") (pintype "unspecified"))
      (node (ref "C9") (pin "1") (pinfunction "1_1") (pintype "input"))
      (node (ref "H10") (pin "1") (pinfunction "1_1") (pintype "unspecified"))
      (node (ref "H6") (pin "1") (pinfunction "1_1") (pintype "unspecified"))
      (node (ref "H9") (pin "1") (pinfunction "1_1") (pintype "unspecified"))
      (node (ref "J2") (pin "2") (pinfunction "6_2") (pintype "bidirectional"))
      (node (ref "R48") (pin "1") (pinfunction "1_1") (pintype "unspecified"))
      (node (ref "R80") (pin "2") (pinfunction "2_2") (pintype "input"))
      (node (ref "R83") (pin "2") (pinfunction "2_2") (pintype "input"))
      (node (ref "R84") (pin "2") (pinfunction "2_2") (pintype "input"))
      (node (ref "R87") (pin "1") (pinfunction "1_1") (pintype "unspecified"))
      (node (ref "R88") (pin "1") (pinfunction "1_1") (pintype "unspecified"))
      (node (ref "U17") (pin "1") (pinfunction "+VS_1") (pintype "unspecified"))
      (node (ref "U29") (pin "8") (pinfunction "VCC_8") (pintype "unspecified"))
      (node (ref "U3") (pin "1") (pinfunction "OUT_1") (pintype "unspecified"))
      (node (ref "U34") (pin "14") (pinfunction "VCC_14") (pintype "unspecified"))
      (node (ref "U36") (pin "2") (pinfunction "VCC_2") (pintype "unspecified"))
    )
    (net (code "56") (name "SENSE_5V_EN") (class "Default")
      (node (ref "U3") (pin "4") (pinfunction "EN_4") (pintype "unspecified"))
      (node (ref "U35") (pin "38") (pinfunction "GPIO34_38") (pintype "bidirectional"))
    )
    (net (code "57") (name "SLR1_N") (class "Default")
      (node (ref "R4") (pin "1") (pinfunction "1_1") (pintype "unspecified"))
      (node (ref "U35") (pin "34") (pinfunction "GPIO36_34") (pintype "bidirectional"))
    )
    (net (code "58") (name "SLR1_P") (class "Default")
      (node (ref "R5") (pin "1") (pinfunction "1_1") (pintype "unspecified"))
      (node (ref "U35") (pin "35") (pinfunction "GPIO35_35") (pintype "bidirectional"))
    )
    (net (code "59") (name "SLR2_N") (class "Default")
      (node (ref "R14") (pin "1") (pinfunction "1_1") (pintype "unspecified"))
      (node (ref "U35") (pin "40") (pinfunction "GPIO21_40") (pintype "bidirectional"))
    )
    (net (code "60") (name "SLR2_P") (class "Default")
      (node (ref "R15") (pin "1") (pinfunction "1_1") (pintype "unspecified"))
      (node (ref "U35") (pin "39") (pinfunction "GPIO33_39") (pintype "bidirectional"))
    )
    (net (code "61") (name "SLR_5V") (class "Default")
      (node (ref "C12") (pin "1") (pinfunction "1_1") (pintype "input"))
      (node (ref "C2") (pin "2") (pinfunction "2_2") (pintype "unspecified"))
      (node (ref "C5") (pin "2") (pinfunction "2_2") (pintype "unspecified"))
      (node (ref "H1") (pin "1") (pinfunction "1_1") (pintype "input"))
      (node (ref "H2") (pin "1") (pinfunction "1_1") (pintype "input"))
      (node (ref "R11") (pin "1") (pinfunction "1_1") (pintype "unspecified"))
      (node (ref "U19") (pin "2") (pinfunction "VDD1_2") (pintype "unspecified"))
      (node (ref "U19") (pin "3") (pinfunction "VDD2_3") (pintype "unspecified"))
      (node (ref "U2") (pin "6") (pinfunction "6_6") (pintype "unspecified"))
      (node (ref "U2") (pin "8") (pinfunction "8_8") (pintype "unspecified"))
      (node (ref "U20") (pin "1") (pinfunction "1_1") (pintype "unspecified"))
      (node (ref "U4") (pin "1") (pinfunction "OUT_1") (pintype "unspecified"))
      (node (ref "U7") (pin "6") (pinfunction "6_6") (pintype "unspecified"))
      (node (ref "U7") (pin "8") (pinfunction "8_8") (pintype "unspecified"))
      (node (ref "U9") (pin "1") (pinfunction "1_1") (pintype "unspecified"))
    )
    (net (code "62") (name "SLR_5V_EN") (class "Default")
      (node (ref "U35") (pin "15") (pinfunction "GPIO09_15") (pintype "bidirectional"))
      (node (ref "U4") (pin "4") (pinfunction "EN_4") (pintype "unspecified"))
    )
    (net (code "63") (name "SN1LED") (class "Default")
      (node (ref "R3") (pin "2") (pinfunction "2_2") (pintype "unspecified"))
      (node (ref "SR5") (pin "2") (pinfunction "+_2") (pintype "input"))
    )
    (net (code "64") (name "SN2LED") (class "Default")
      (node (ref "R13") (pin "2") (pinfunction "2_2") (pintype "unspecified"))
      (node (ref "SR2") (pin "2") (pinfunction "+_2") (pintype "input"))
    )
    (net (code "65") (name "SP1LED") (class "Default")
      (node (ref "R2") (pin "2") (pinfunction "2_2") (pintype "unspecified"))
      (node (ref "SR6") (pin "1") (pinfunction "A_1") (pintype "input"))
    )
    (net (code "66") (name "SP2LED") (class "Default")
      (node (ref "R12") (pin "2") (pinfunction "2_2") (pintype "unspecified"))
      (node (ref "SR1") (pin "1") (pinfunction "A_1") (pintype "input"))
    )
    (net (code "67") (name "VI-1") (class "Default")
      (node (ref "H6") (pin "4") (pinfunction "4_4") (pintype "unspecified"))
      (node (ref "R46") (pin "1") (pinfunction "1_1") (pintype "unspecified"))
    )
    (net (code "68") (name "VI-2") (class "Default")
      (node (ref "H6") (pin "3") (pinfunction "3_3") (pintype "unspecified"))
      (node (ref "R44") (pin "1") (pinfunction "1_1") (pintype "unspecified"))
    )
    (net (code "69") (name "VI-3") (class "Default")
      (node (ref "H9") (pin "3") (pinfunction "3_3") (pintype "unspecified"))
      (node (ref "R47") (pin "1") (pinfunction "1_1") (pintype "unspecified"))
      (node (ref "R49") (pin "1") (pinfunction "1_1") (pintype "unspecified"))
    )
    (net (code "70") (name "VI-4") (class "Default")
      (node (ref "H9") (pin "4") (pinfunction "4_4") (pintype "unspecified"))
      (node (ref "R48") (pin "2") (pinfunction "2_2") (pintype "unspecified"))
      (node (ref "R51") (pin "1") (pinfunction "1_1") (pintype "unspecified"))
    )
    (net (code "71") (name "VIN+5V") (class "Default")
      (node (ref "CN2") (pin "1") (pinfunction "1_1") (pintype "input"))
      (node (ref "D7") (pin "2") (pinfunction "2_2") (pintype "unspecified"))
      (node (ref "D8") (pin "2") (pinfunction "2_2") (pintype "unspecified"))
    )
    (net (code "72") (name "VIN1") (class "Default")
      (node (ref "R45") (pin "1") (pinfunction "1_1") (pintype "unspecified"))
      (node (ref "R46") (pin "2") (pinfunction "2_2") (pintype "unspecified"))
      (node (ref "SGV6") (pin "2") (pinfunction "2_2") (pintype "unspecified"))
      (node (ref "U35") (pin "4") (pinfunction "GPIO04_4") (pintype "bidirectional"))
    )
    (net (code "73") (name "VIN2") (class "Default")
      (node (ref "R43") (pin "1") (pinfunction "1_1") (pintype "unspecified"))
      (node (ref "R44") (pin "2") (pinfunction "2_2") (pintype "unspecified"))
      (node (ref "SGV5") (pin "2") (pinfunction "2_2") (pintype "unspecified"))
      (node (ref "U35") (pin "5") (pinfunction "GPIO05_5") (pintype "bidirectional"))
    )
    (net (code "74") (name "VIN3") (class "Default")
      (node (ref "R49") (pin "2") (pinfunction "2_2") (pintype "unspecified"))
      (node (ref "R50") (pin "1") (pinfunction "1_1") (pintype "unspecified"))
      (node (ref "SGV7") (pin "2") (pinfunction "2_2") (pintype "unspecified"))
      (node (ref "U35") (pin "6") (pinfunction "GPIO06_6") (pintype "bidirectional"))
    )
    (net (code "75") (name "VIN4") (class "Default")
      (node (ref "R51") (pin "2") (pinfunction "2_2") (pintype "unspecified"))
      (node (ref "R52") (pin "1") (pinfunction "1_1") (pintype "unspecified"))
      (node (ref "SGV8") (pin "2") (pinfunction "2_2") (pintype "unspecified"))
      (node (ref "U35") (pin "7") (pinfunction "GPIO07_7") (pintype "bidirectional"))
    )
    (net (code "76") (name "unconnected-(J2-4-Pad6)") (class "Default")
      (node (ref "J2") (pin "6") (pinfunction "4_6") (pintype "bidirectional+no_connect"))
    )
    (net (code "77") (name "unconnected-(J2-5-Pad4)") (class "Default")
      (node (ref "J2") (pin "4") (pinfunction "5_4") (pintype "bidirectional+no_connect"))
    )
    (net (code "78") (name "unconnected-(SW2-Pad0)") (class "Default")
      (node (ref "SW2") (pin "0") (pinfunction "0_0") (pintype "unspecified+no_connect"))
    )
    (net (code "79") (name "unconnected-(SW2-Pad0)_1") (class "Default")
      (node (ref "SW2") (pin "0") (pinfunction "0_0") (pintype "unspecified+no_connect"))
    )
    (net (code "80") (name "unconnected-(SW2-Pad1)") (class "Default")
      (node (ref "SW2") (pin "1") (pinfunction "1_1") (pintype "unspecified+no_connect"))
    )
    (net (code "81") (name "unconnected-(SW2-Pad6)") (class "Default")
      (node (ref "SW2") (pin "6") (pinfunction "6_6") (pintype "unspecified+no_connect"))
    )
    (net (code "82") (name "unconnected-(U3-FLT#-Pad3)") (class "Default")
      (node (ref "U3") (pin "3") (pinfunction "FLT#_3") (pintype "unspecified+no_connect"))
    )
    (net (code "83") (name "unconnected-(U4-FLT#-Pad3)") (class "Default")
      (node (ref "U4") (pin "3") (pinfunction "FLT#_3") (pintype "unspecified+no_connect"))
    )
    (net (code "84") (name "unconnected-(U35-GPIO00-Pad36)") (class "Default")
      (node (ref "U35") (pin "36") (pinfunction "GPIO00_36") (pintype "bidirectional+no_connect"))
    )
    (net (code "85") (name "unconnected-(U35-GPIO15-Pad8)") (class "Default")
      (node (ref "U35") (pin "8") (pinfunction "GPIO15_8") (pintype "bidirectional+no_connect"))
    )
    (net (code "86") (name "unconnected-(U35-GPIO16-Pad9)") (class "Default")
      (node (ref "U35") (pin "9") (pinfunction "GPIO16_9") (pintype "bidirectional+no_connect"))
    )
    (net (code "87") (name "unconnected-(U35-GPIO19-Pad42)") (class "Default")
      (node (ref "U35") (pin "42") (pinfunction "GPIO19_42") (pintype "bidirectional+no_connect"))
    )
    (net (code "88") (name "unconnected-(U35-GPIO20-Pad41)") (class "Default")
      (node (ref "U35") (pin "41") (pinfunction "GPIO20_41") (pintype "bidirectional+no_connect"))
    )
    (net (code "89") (name "unconnected-(U35-GPIO39-Pad31)") (class "Default")
      (node (ref "U35") (pin "31") (pinfunction "GPIO39_31") (pintype "bidirectional+no_connect"))
    )
    (net (code "90") (name "unconnected-(U35-GPIO40-Pad30)") (class "Default")
      (node (ref "U35") (pin "30") (pinfunction "GPIO40_30") (pintype "bidirectional+no_connect"))
    )
    (net (code "91") (name "unconnected-(U35-GPIO41-Pad29)") (class "Default")
      (node (ref "U35") (pin "29") (pinfunction "GPIO41_29") (pintype "bidirectional+no_connect"))
    )
    (net (code "92") (name "unconnected-(U35-GPIO42-Pad28)") (class "Default")
      (node (ref "U35") (pin "28") (pinfunction "GPIO42_28") (pintype "bidirectional+no_connect"))
    )
    (net (code "93") (name "unconnected-(U35-GPIO43-Pad24)") (class "Default")
      (node (ref "U35") (pin "24") (pinfunction "GPIO43_24") (pintype "bidirectional+no_connect"))
    )
    (net (code "94") (name "unconnected-(U35-GPIO44-Pad25)") (class "Default")
      (node (ref "U35") (pin "25") (pinfunction "GPIO44_25") (pintype "bidirectional+no_connect"))
    )
    (net (code "95") (name "unconnected-(U35-GPIO45-Pad37)") (class "Default")
      (node (ref "U35") (pin "37") (pinfunction "GPIO45_37") (pintype "input+no_connect"))
    )
    (net (code "96") (name "unconnected-(U35-GPIO46-Pad14)") (class "Default")
      (node (ref "U35") (pin "14") (pinfunction "GPIO46_14") (pintype "bidirectional+no_connect"))
    )
  )
)
